# roaster3.net
KiCad netlist of a schematic drawn in EAGLE
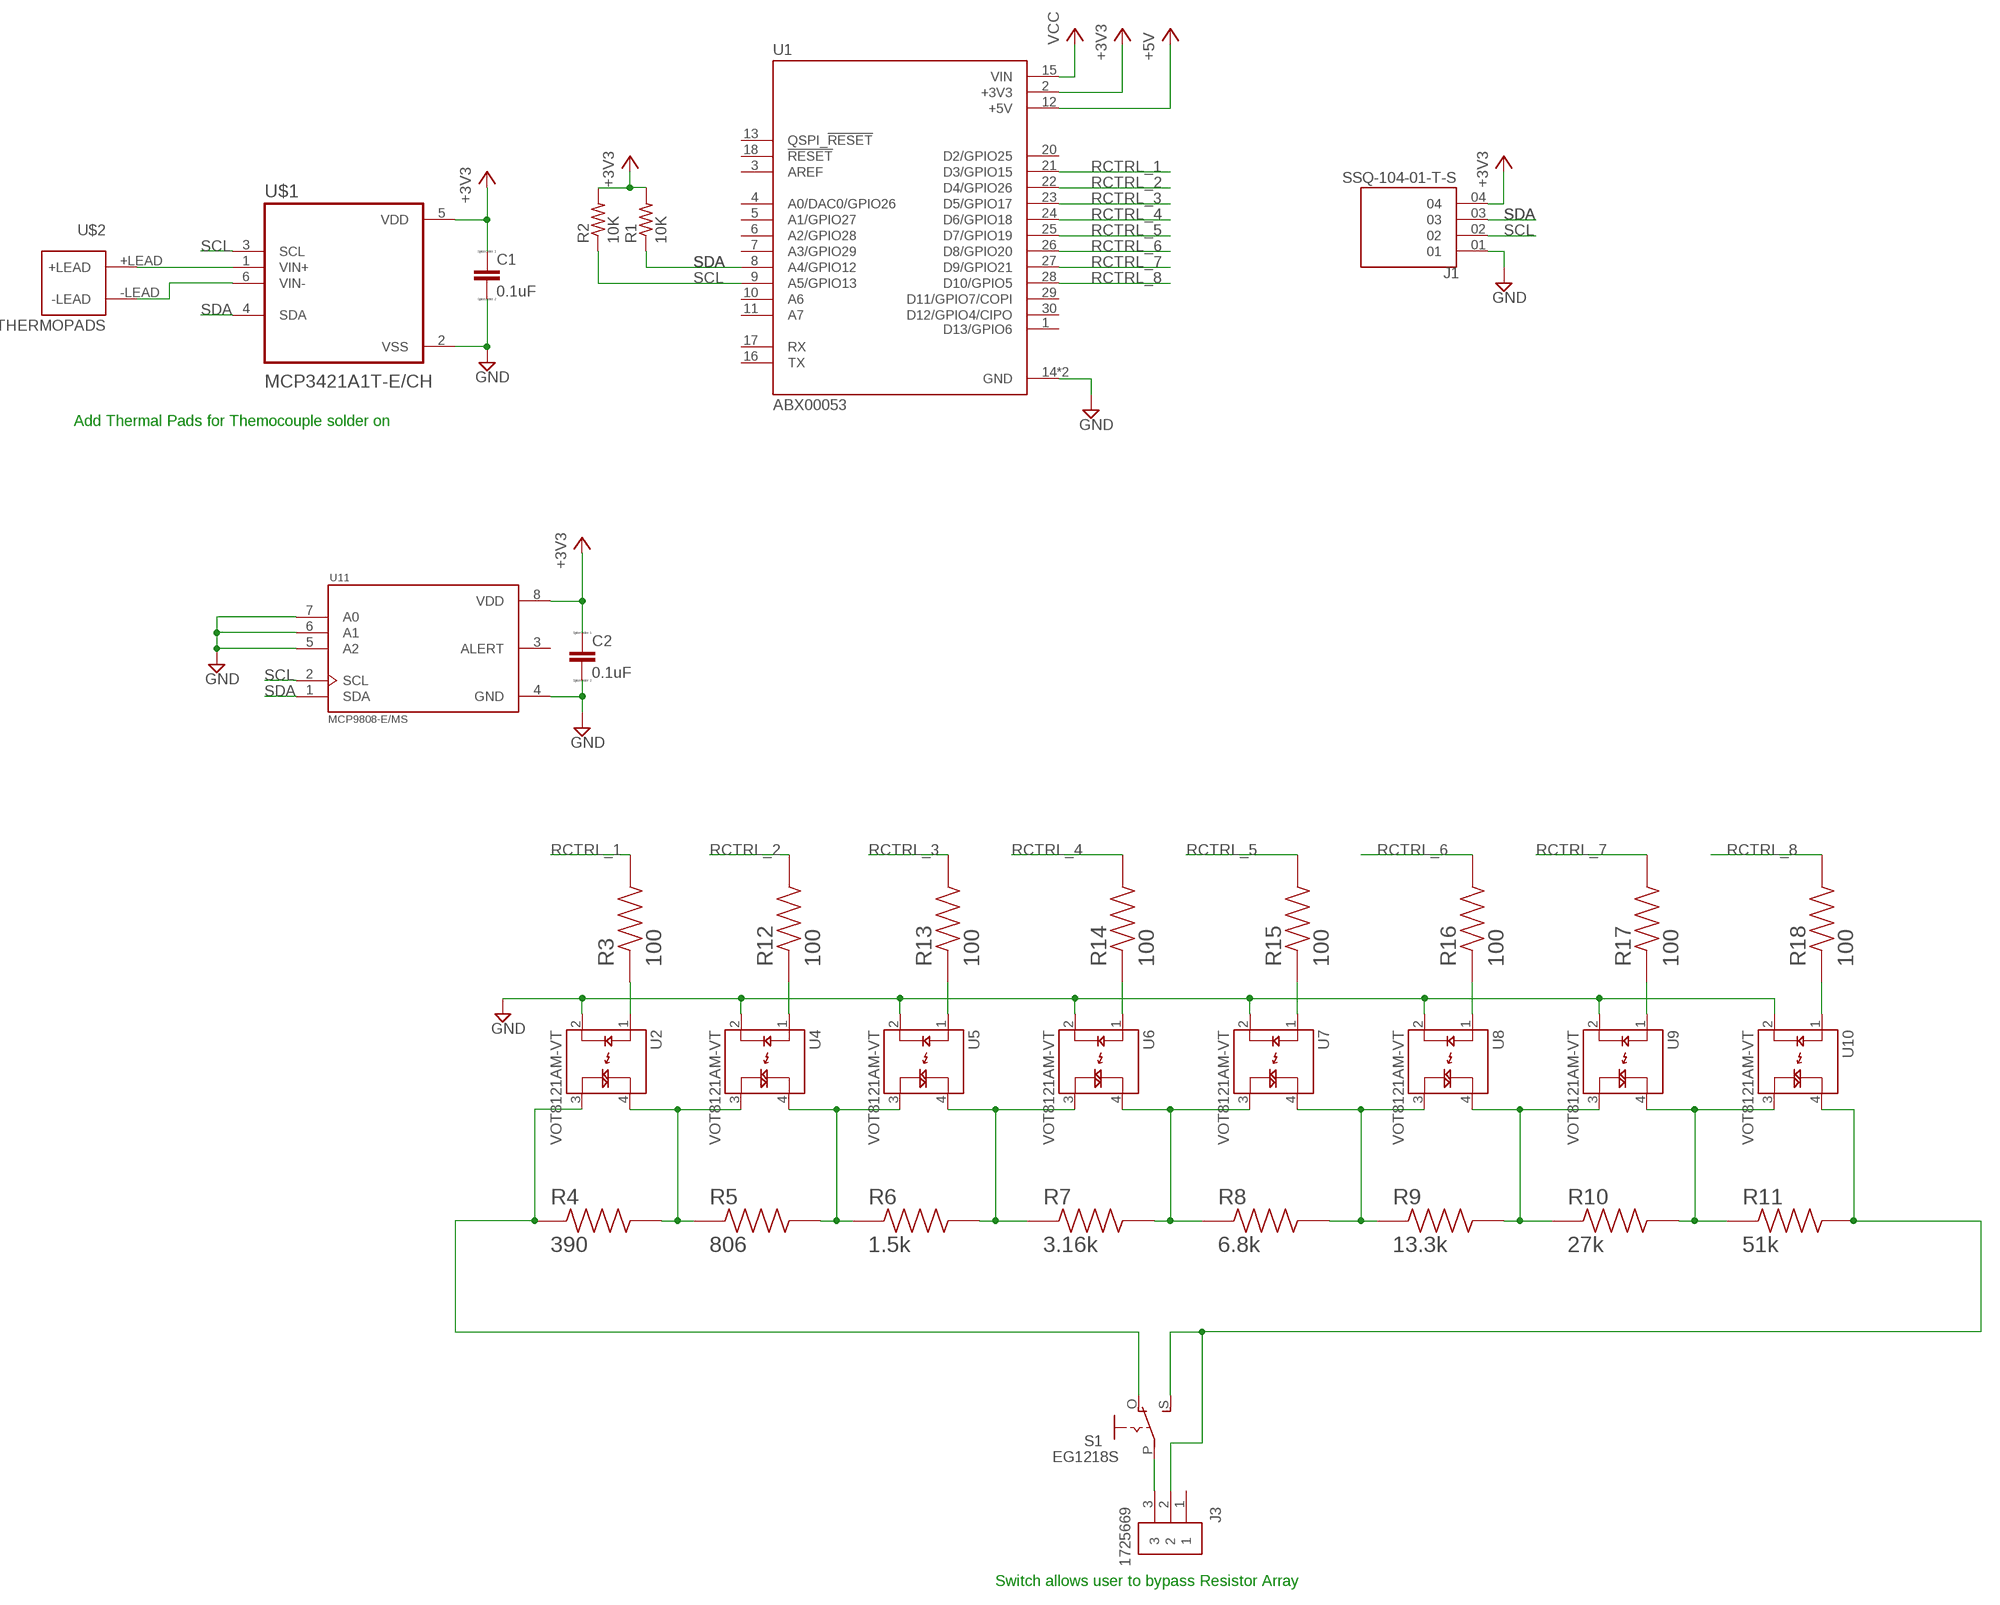
[diagram p0: schematic, sheet 1]

(export (version "E")
  (design (tool "Eeschema 10.0.6"))
  (components
    (comp (ref "C1")
      (value "0.1uF")
      (footprint "eagle-import:RUNJUMP_C0603")
      (fields (field (name "MFR") "Samsung Electro-Mechanics") (field (name "VOLTAGE") "25V"))
      (libsource (lib "eagle-import") (part "RUNJUMP_CAPACITOR-0603-0.1UF-DECOUPLING"))
    )
    (comp (ref "C2")
      (value "0.1uF")
      (footprint "eagle-import:RUNJUMP_C0603")
      (fields (field (name "MFR") "Samsung Electro-Mechanics") (field (name "VOLTAGE") "25V"))
      (libsource (lib "eagle-import") (part "RUNJUMP_CAPACITOR-0603-0.1UF-DECOUPLING"))
    )
    (comp (ref "J1")
      (value "SSQ-104-01-T-S")
      (footprint "eagle-import:SAMTEC_SSQ-104-01-T-S")
      (fields (field (name "MF") "Samtec Inc."))
      (libsource (lib "eagle-import") (part "SSQ-104-01-T-S"))
    )
    (comp (ref "J3")
      (value "1725669")
      (footprint "eagle-import:PHOENIX_1725669")
      (fields (field (name "MF") "Phoenix Contact"))
      (libsource (lib "eagle-import") (part "1725669"))
    )
    (comp (ref "R1")
      (value "10K")
      (footprint "eagle-import:RUNJUMP_R0603")
      (fields (field (name "MFR") "Samsung Electro-Mechanics") (field (name "TOLERANCE") "5%"))
      (libsource (lib "eagle-import") (part "RUNJUMP_RESISTOR-10K"))
    )
    (comp (ref "R2")
      (value "10K")
      (footprint "eagle-import:RUNJUMP_R0603")
      (fields (field (name "MFR") "Samsung Electro-Mechanics") (field (name "TOLERANCE") "5%"))
      (libsource (lib "eagle-import") (part "RUNJUMP_RESISTOR-10K"))
    )
    (comp (ref "R3")
      (value "100")
      (footprint "eagle-import:RESC1608X55N")
      (fields (field (name "MF") "Yageo") (field (name "MP") "AC0603FR-10100RL"))
      (libsource (lib "eagle-import") (part "AC0603FR-10100RL"))
    )
    (comp (ref "R4")
      (value "390")
      (footprint "eagle-import:RESC6332X70N")
      (fields (field (name "MF") "Stackpole Electronics Inc") (field (name "MP") "RMCF2512JT390R"))
      (libsource (lib "eagle-import") (part "RMCF2512JT390R"))
    )
    (comp (ref "R5")
      (value "806")
      (footprint "eagle-import:RESC6332X70N")
      (libsource (lib "eagle-import") (part "RMCF2512FT806R"))
    )
    (comp (ref "R6")
      (value "1.5k")
      (footprint "eagle-import:RESC6332X70N")
      (fields (field (name "MF") "Stackpole Electronics Inc"))
      (libsource (lib "eagle-import") (part "RMCF2512JT1K50"))
    )
    (comp (ref "R7")
      (value "3.16k")
      (footprint "eagle-import:RESC6332X70N")
      (fields (field (name "MF") "Stackpole Electronics Inc"))
      (libsource (lib "eagle-import") (part "RMCF2512FT3K16"))
    )
    (comp (ref "R8")
      (value "6.8k")
      (footprint "eagle-import:RESC6332X70N")
      (fields (field (name "MF") "Stackpole Electronics Inc"))
      (libsource (lib "eagle-import") (part "RMCF2512JT6K80"))
    )
    (comp (ref "R9")
      (value "13.3k")
      (footprint "eagle-import:RESC6332X70N")
      (fields (field (name "MF") "Stackpole Electronics Inc"))
      (libsource (lib "eagle-import") (part "RMCF2512FT13K3"))
    )
    (comp (ref "R10")
      (value "27k")
      (footprint "eagle-import:RESC6332X70N")
      (fields (field (name "MF") "Stackpole Electronics Inc"))
      (libsource (lib "eagle-import") (part "RMCF2512JT27K0"))
    )
    (comp (ref "R11")
      (value "51k")
      (footprint "eagle-import:RESC6332X70N")
      (fields (field (name "MF") "Stackpole Electronics Inc"))
      (libsource (lib "eagle-import") (part "RMCF2512JT51K0"))
    )
    (comp (ref "R12")
      (value "100")
      (footprint "eagle-import:RESC1608X55N")
      (fields (field (name "MF") "Yageo") (field (name "MP") "AC0603FR-10100RL"))
      (libsource (lib "eagle-import") (part "AC0603FR-10100RL"))
    )
    (comp (ref "R13")
      (value "100")
      (footprint "eagle-import:RESC1608X55N")
      (fields (field (name "MF") "Yageo") (field (name "MP") "AC0603FR-10100RL"))
      (libsource (lib "eagle-import") (part "AC0603FR-10100RL"))
    )
    (comp (ref "R14")
      (value "100")
      (footprint "eagle-import:RESC1608X55N")
      (fields (field (name "MF") "Yageo") (field (name "MP") "AC0603FR-10100RL"))
      (libsource (lib "eagle-import") (part "AC0603FR-10100RL"))
    )
    (comp (ref "R15")
      (value "100")
      (footprint "eagle-import:RESC1608X55N")
      (fields (field (name "MF") "Yageo") (field (name "MP") "AC0603FR-10100RL"))
      (libsource (lib "eagle-import") (part "AC0603FR-10100RL"))
    )
    (comp (ref "R16")
      (value "100")
      (footprint "eagle-import:RESC1608X55N")
      (fields (field (name "MF") "Yageo") (field (name "MP") "AC0603FR-10100RL"))
      (libsource (lib "eagle-import") (part "AC0603FR-10100RL"))
    )
    (comp (ref "R17")
      (value "100")
      (footprint "eagle-import:RESC1608X55N")
      (fields (field (name "MF") "Yageo") (field (name "MP") "AC0603FR-10100RL"))
      (libsource (lib "eagle-import") (part "AC0603FR-10100RL"))
    )
    (comp (ref "R18")
      (value "100")
      (footprint "eagle-import:RESC1608X55N")
      (fields (field (name "MF") "Yageo") (field (name "MP") "AC0603FR-10100RL"))
      (libsource (lib "eagle-import") (part "AC0603FR-10100RL"))
    )
    (comp (ref "S1")
      (value "EG1218S")
      (footprint "eagle-import:EG1218")
      (fields (field (name "MF") "E-Switch") (field (name "MP") "EG1218."))
      (libsource (lib "eagle-import") (part "EG1218S"))
    )
    (comp (ref "U$1")
      (value "MCP3421A1T-E/CH")
      (footprint "eagle-import:SOT95P280X145-6N")
      (fields (field (name "MF") "Microchip Technology"))
      (libsource (lib "eagle-import") (part "MCP3421A1T-E/CH"))
    )
    (comp (ref "U$2")
      (value "THERMOPADS")
      (footprint "eagle-import:THERMOPADS")
      (libsource (lib "eagle-import") (part "THERMOPADS"))
    )
    (comp (ref "U1")
      (value "ABX00053")
      (footprint "eagle-import:MODULE_ABX00053")
      (fields (field (name "DIGI-KEY_PART_NUMBER") "1050-ABX00053-ND") (field (name "MF") "Arduino"))
      (libsource (lib "eagle-import") (part "ABX00053"))
    )
    (comp (ref "U2")
      (value "VOT8121AM-VT")
      (footprint "eagle-import:SOIC254P675X240-4N")
      (fields (field (name "MF") "Vishay Semiconductor Opto Division"))
      (libsource (lib "eagle-import") (part "VOT8121AM-VT"))
    )
    (comp (ref "U4")
      (value "VOT8121AM-VT")
      (footprint "eagle-import:SOIC254P675X240-4N")
      (fields (field (name "MF") "Vishay Semiconductor Opto Division"))
      (libsource (lib "eagle-import") (part "VOT8121AM-VT"))
    )
    (comp (ref "U5")
      (value "VOT8121AM-VT")
      (footprint "eagle-import:SOIC254P675X240-4N")
      (fields (field (name "MF") "Vishay Semiconductor Opto Division"))
      (libsource (lib "eagle-import") (part "VOT8121AM-VT"))
    )
    (comp (ref "U6")
      (value "VOT8121AM-VT")
      (footprint "eagle-import:SOIC254P675X240-4N")
      (fields (field (name "MF") "Vishay Semiconductor Opto Division"))
      (libsource (lib "eagle-import") (part "VOT8121AM-VT"))
    )
    (comp (ref "U7")
      (value "VOT8121AM-VT")
      (footprint "eagle-import:SOIC254P675X240-4N")
      (fields (field (name "MF") "Vishay Semiconductor Opto Division"))
      (libsource (lib "eagle-import") (part "VOT8121AM-VT"))
    )
    (comp (ref "U8")
      (value "VOT8121AM-VT")
      (footprint "eagle-import:SOIC254P675X240-4N")
      (fields (field (name "MF") "Vishay Semiconductor Opto Division"))
      (libsource (lib "eagle-import") (part "VOT8121AM-VT"))
    )
    (comp (ref "U9")
      (value "VOT8121AM-VT")
      (footprint "eagle-import:SOIC254P675X240-4N")
      (fields (field (name "MF") "Vishay Semiconductor Opto Division"))
      (libsource (lib "eagle-import") (part "VOT8121AM-VT"))
    )
    (comp (ref "U10")
      (value "VOT8121AM-VT")
      (footprint "eagle-import:SOIC254P675X240-4N")
      (fields (field (name "MF") "Vishay Semiconductor Opto Division"))
      (libsource (lib "eagle-import") (part "VOT8121AM-VT"))
    )
    (comp (ref "U11")
      (value "MCP9808-E/MS")
      (footprint "eagle-import:SOP65P490X110-8N")
      (fields (field (name "MF") "Microchip"))
      (libsource (lib "eagle-import") (part "MCP9808-E/MS"))
    )
  )
  (nets
    (net (code "1") (name "+3V3") (class "Default")
      (node (ref "C1") (pin "1") (pinfunction "1_1") (pintype "passive"))
      (node (ref "C2") (pin "1") (pinfunction "1_1") (pintype "passive"))
      (node (ref "J1") (pin "04") (pinfunction "04_04") (pintype "passive"))
      (node (ref "R1") (pin "2") (pinfunction "2_2") (pintype "passive"))
      (node (ref "R2") (pin "2") (pinfunction "2_2") (pintype "passive"))
      (node (ref "U$1") (pin "5") (pinfunction "VDD_5") (pintype "power_in"))
      (node (ref "U1") (pin "2") (pinfunction "+3V3_2") (pintype "power_in"))
      (node (ref "U11") (pin "8") (pinfunction "VDD_8") (pintype "power_in"))
    )
    (net (code "2") (name "+5V") (class "Default")
      (node (ref "U1") (pin "12") (pinfunction "+5V_12") (pintype "power_in"))
    )
    (net (code "3") (name "/RCTRL_1") (class "Default")
      (node (ref "R3") (pin "2") (pinfunction "2_2") (pintype "passive"))
      (node (ref "U1") (pin "21") (pinfunction "D3/GPIO15_21") (pintype "bidirectional"))
    )
    (net (code "4") (name "/RCTRL_2") (class "Default")
      (node (ref "R12") (pin "2") (pinfunction "2_2") (pintype "passive"))
      (node (ref "U1") (pin "22") (pinfunction "D4/GPIO26_22") (pintype "bidirectional"))
    )
    (net (code "5") (name "/RCTRL_3") (class "Default")
      (node (ref "R13") (pin "2") (pinfunction "2_2") (pintype "passive"))
      (node (ref "U1") (pin "23") (pinfunction "D5/GPIO17_23") (pintype "bidirectional"))
    )
    (net (code "6") (name "/RCTRL_4") (class "Default")
      (node (ref "R14") (pin "2") (pinfunction "2_2") (pintype "passive"))
      (node (ref "U1") (pin "24") (pinfunction "D6/GPIO18_24") (pintype "bidirectional"))
    )
    (net (code "7") (name "/RCTRL_5") (class "Default")
      (node (ref "R15") (pin "2") (pinfunction "2_2") (pintype "passive"))
      (node (ref "U1") (pin "25") (pinfunction "D7/GPIO19_25") (pintype "bidirectional"))
    )
    (net (code "8") (name "/RCTRL_6") (class "Default")
      (node (ref "R16") (pin "2") (pinfunction "2_2") (pintype "passive"))
      (node (ref "U1") (pin "26") (pinfunction "D8/GPIO20_26") (pintype "bidirectional"))
    )
    (net (code "9") (name "/RCTRL_7") (class "Default")
      (node (ref "R17") (pin "2") (pinfunction "2_2") (pintype "passive"))
      (node (ref "U1") (pin "27") (pinfunction "D9/GPIO21_27") (pintype "bidirectional"))
    )
    (net (code "10") (name "/RCTRL_8") (class "Default")
      (node (ref "R18") (pin "2") (pinfunction "2_2") (pintype "passive"))
      (node (ref "U1") (pin "28") (pinfunction "D10/GPIO5_28") (pintype "bidirectional"))
    )
    (net (code "11") (name "/SCL") (class "Default")
      (node (ref "J1") (pin "02") (pinfunction "02_02") (pintype "passive"))
      (node (ref "R2") (pin "1") (pinfunction "1_1") (pintype "passive"))
      (node (ref "U$1") (pin "3") (pinfunction "SCL_3") (pintype "input"))
      (node (ref "U1") (pin "9") (pinfunction "A5/GPIO13_9") (pintype "bidirectional"))
      (node (ref "U11") (pin "2") (pinfunction "SCL_2") (pintype "input"))
    )
    (net (code "12") (name "/SDA") (class "Default")
      (node (ref "J1") (pin "03") (pinfunction "03_03") (pintype "passive"))
      (node (ref "R1") (pin "1") (pinfunction "1_1") (pintype "passive"))
      (node (ref "U$1") (pin "4") (pinfunction "SDA_4") (pintype "bidirectional"))
      (node (ref "U1") (pin "8") (pinfunction "A4/GPIO12_8") (pintype "bidirectional"))
      (node (ref "U11") (pin "1") (pinfunction "SDA_1") (pintype "bidirectional"))
    )
    (net (code "13") (name "GND") (class "Default")
      (node (ref "C1") (pin "2") (pinfunction "2_2") (pintype "passive"))
      (node (ref "C2") (pin "2") (pinfunction "2_2") (pintype "passive"))
      (node (ref "J1") (pin "01") (pinfunction "01_01") (pintype "passive"))
      (node (ref "U$1") (pin "2") (pinfunction "VSS_2") (pintype "power_in"))
      (node (ref "U1") (pin "14") (pinfunction "GND_14") (pintype "power_in"))
      (node (ref "U1") (pin "19") (pinfunction "GND_19") (pintype "power_in"))
      (node (ref "U10") (pin "2") (pinfunction "C_2") (pintype "passive"))
      (node (ref "U11") (pin "4") (pinfunction "GND_4") (pintype "power_in"))
      (node (ref "U11") (pin "5") (pinfunction "A2_5") (pintype "input"))
      (node (ref "U11") (pin "6") (pinfunction "A1_6") (pintype "input"))
      (node (ref "U11") (pin "7") (pinfunction "A0_7") (pintype "input"))
      (node (ref "U2") (pin "2") (pinfunction "C_2") (pintype "passive"))
      (node (ref "U4") (pin "2") (pinfunction "C_2") (pintype "passive"))
      (node (ref "U5") (pin "2") (pinfunction "C_2") (pintype "passive"))
      (node (ref "U6") (pin "2") (pinfunction "C_2") (pintype "passive"))
      (node (ref "U7") (pin "2") (pinfunction "C_2") (pintype "passive"))
      (node (ref "U8") (pin "2") (pinfunction "C_2") (pintype "passive"))
      (node (ref "U9") (pin "2") (pinfunction "C_2") (pintype "passive"))
    )
    (net (code "14") (name "Net-(J3-Pad3)") (class "Default")
      (node (ref "J3") (pin "3") (pinfunction "3_3") (pintype "passive"))
      (node (ref "S1") (pin "P") (pinfunction "P_P") (pintype "passive"))
    )
    (net (code "15") (name "Net-(U$1-VIN+)") (class "Default")
      (node (ref "U$1") (pin "1") (pinfunction "VIN+_1") (pintype "input"))
      (node (ref "U$2") (pin "+LEAD") (pinfunction "+LEAD_+LEAD") (pintype "bidirectional"))
    )
    (net (code "16") (name "Net-(U$1-VIN-)") (class "Default")
      (node (ref "U$1") (pin "6") (pinfunction "VIN-_6") (pintype "input"))
      (node (ref "U$2") (pin "-LEAD") (pinfunction "-LEAD_-LEAD") (pintype "bidirectional"))
    )
    (net (code "17") (name "Net-(U2-A)") (class "Default")
      (node (ref "R3") (pin "1") (pinfunction "1_1") (pintype "passive"))
      (node (ref "U2") (pin "1") (pinfunction "A_1") (pintype "passive"))
    )
    (net (code "18") (name "Net-(U2-MT1)") (class "Default")
      (node (ref "R4") (pin "1") (pinfunction "1_1") (pintype "passive"))
      (node (ref "S1") (pin "O") (pinfunction "O_O") (pintype "passive"))
      (node (ref "U2") (pin "3") (pinfunction "MT1_3") (pintype "passive"))
    )
    (net (code "19") (name "Net-(U2-MT2)") (class "Default")
      (node (ref "R4") (pin "2") (pinfunction "2_2") (pintype "passive"))
      (node (ref "R5") (pin "1") (pinfunction "1_1") (pintype "passive"))
      (node (ref "U2") (pin "4") (pinfunction "MT2_4") (pintype "passive"))
      (node (ref "U4") (pin "3") (pinfunction "MT1_3") (pintype "passive"))
    )
    (net (code "20") (name "Net-(U4-A)") (class "Default")
      (node (ref "R12") (pin "1") (pinfunction "1_1") (pintype "passive"))
      (node (ref "U4") (pin "1") (pinfunction "A_1") (pintype "passive"))
    )
    (net (code "21") (name "Net-(U4-MT2)") (class "Default")
      (node (ref "R5") (pin "2") (pinfunction "2_2") (pintype "passive"))
      (node (ref "R6") (pin "1") (pinfunction "1_1") (pintype "passive"))
      (node (ref "U4") (pin "4") (pinfunction "MT2_4") (pintype "passive"))
      (node (ref "U5") (pin "3") (pinfunction "MT1_3") (pintype "passive"))
    )
    (net (code "22") (name "Net-(U5-A)") (class "Default")
      (node (ref "R13") (pin "1") (pinfunction "1_1") (pintype "passive"))
      (node (ref "U5") (pin "1") (pinfunction "A_1") (pintype "passive"))
    )
    (net (code "23") (name "Net-(U5-MT2)") (class "Default")
      (node (ref "R6") (pin "2") (pinfunction "2_2") (pintype "passive"))
      (node (ref "R7") (pin "1") (pinfunction "1_1") (pintype "passive"))
      (node (ref "U5") (pin "4") (pinfunction "MT2_4") (pintype "passive"))
      (node (ref "U6") (pin "3") (pinfunction "MT1_3") (pintype "passive"))
    )
    (net (code "24") (name "Net-(U6-A)") (class "Default")
      (node (ref "R14") (pin "1") (pinfunction "1_1") (pintype "passive"))
      (node (ref "U6") (pin "1") (pinfunction "A_1") (pintype "passive"))
    )
    (net (code "25") (name "Net-(U6-MT2)") (class "Default")
      (node (ref "R7") (pin "2") (pinfunction "2_2") (pintype "passive"))
      (node (ref "R8") (pin "1") (pinfunction "1_1") (pintype "passive"))
      (node (ref "U6") (pin "4") (pinfunction "MT2_4") (pintype "passive"))
      (node (ref "U7") (pin "3") (pinfunction "MT1_3") (pintype "passive"))
    )
    (net (code "26") (name "Net-(U7-A)") (class "Default")
      (node (ref "R15") (pin "1") (pinfunction "1_1") (pintype "passive"))
      (node (ref "U7") (pin "1") (pinfunction "A_1") (pintype "passive"))
    )
    (net (code "27") (name "Net-(U7-MT2)") (class "Default")
      (node (ref "R8") (pin "2") (pinfunction "2_2") (pintype "passive"))
      (node (ref "R9") (pin "1") (pinfunction "1_1") (pintype "passive"))
      (node (ref "U7") (pin "4") (pinfunction "MT2_4") (pintype "passive"))
      (node (ref "U8") (pin "3") (pinfunction "MT1_3") (pintype "passive"))
    )
    (net (code "28") (name "Net-(U8-A)") (class "Default")
      (node (ref "R16") (pin "1") (pinfunction "1_1") (pintype "passive"))
      (node (ref "U8") (pin "1") (pinfunction "A_1") (pintype "passive"))
    )
    (net (code "29") (name "Net-(U8-MT2)") (class "Default")
      (node (ref "R10") (pin "1") (pinfunction "1_1") (pintype "passive"))
      (node (ref "R9") (pin "2") (pinfunction "2_2") (pintype "passive"))
      (node (ref "U8") (pin "4") (pinfunction "MT2_4") (pintype "passive"))
      (node (ref "U9") (pin "3") (pinfunction "MT1_3") (pintype "passive"))
    )
    (net (code "30") (name "Net-(U9-A)") (class "Default")
      (node (ref "R17") (pin "1") (pinfunction "1_1") (pintype "passive"))
      (node (ref "U9") (pin "1") (pinfunction "A_1") (pintype "passive"))
    )
    (net (code "31") (name "Net-(U10-A)") (class "Default")
      (node (ref "R18") (pin "1") (pinfunction "1_1") (pintype "passive"))
      (node (ref "U10") (pin "1") (pinfunction "A_1") (pintype "passive"))
    )
    (net (code "32") (name "Net-(U10-MT1)") (class "Default")
      (node (ref "R10") (pin "2") (pinfunction "2_2") (pintype "passive"))
      (node (ref "R11") (pin "1") (pinfunction "1_1") (pintype "passive"))
      (node (ref "U10") (pin "3") (pinfunction "MT1_3") (pintype "passive"))
      (node (ref "U9") (pin "4") (pinfunction "MT2_4") (pintype "passive"))
    )
    (net (code "33") (name "Net-(U10-MT2)") (class "Default")
      (node (ref "J3") (pin "2") (pinfunction "2_2") (pintype "passive"))
      (node (ref "R11") (pin "2") (pinfunction "2_2") (pintype "passive"))
      (node (ref "S1") (pin "S") (pinfunction "S_S") (pintype "passive"))
      (node (ref "U10") (pin "4") (pinfunction "MT2_4") (pintype "passive"))
    )
    (net (code "34") (name "VCC") (class "Default")
      (node (ref "U1") (pin "15") (pinfunction "VIN_15") (pintype "power_in"))
    )
    (net (code "35") (name "unconnected-(J3-Pad1)") (class "Default")
      (node (ref "J3") (pin "1") (pinfunction "1_1") (pintype "passive"))
    )
    (net (code "36") (name "unconnected-(U1-A0{slash}DAC0{slash}GPIO26-Pad4)") (class "Default")
      (node (ref "U1") (pin "4") (pinfunction "A0/DAC0/GPIO26_4") (pintype "bidirectional"))
    )
    (net (code "37") (name "unconnected-(U1-A1{slash}GPIO27-Pad5)") (class "Default")
      (node (ref "U1") (pin "5") (pinfunction "A1/GPIO27_5") (pintype "bidirectional"))
    )
    (net (code "38") (name "unconnected-(U1-A2{slash}GPIO28-Pad6)") (class "Default")
      (node (ref "U1") (pin "6") (pinfunction "A2/GPIO28_6") (pintype "bidirectional"))
    )
    (net (code "39") (name "unconnected-(U1-A3{slash}GPIO29-Pad7)") (class "Default")
      (node (ref "U1") (pin "7") (pinfunction "A3/GPIO29_7") (pintype "bidirectional"))
    )
    (net (code "40") (name "unconnected-(U1-A6-Pad10)") (class "Default")
      (node (ref "U1") (pin "10") (pinfunction "A6_10") (pintype "bidirectional"))
    )
    (net (code "41") (name "unconnected-(U1-A7-Pad11)") (class "Default")
      (node (ref "U1") (pin "11") (pinfunction "A7_11") (pintype "bidirectional"))
    )
    (net (code "42") (name "unconnected-(U1-AREF-Pad3)") (class "Default")
      (node (ref "U1") (pin "3") (pinfunction "AREF_3") (pintype "bidirectional"))
    )
    (net (code "43") (name "unconnected-(U1-D2{slash}GPIO25-Pad20)") (class "Default")
      (node (ref "U1") (pin "20") (pinfunction "D2/GPIO25_20") (pintype "bidirectional"))
    )
    (net (code "44") (name "unconnected-(U1-D11{slash}GPIO7{slash}COPI-Pad29)") (class "Default")
      (node (ref "U1") (pin "29") (pinfunction "D11/GPIO7/COPI_29") (pintype "bidirectional"))
    )
    (net (code "45") (name "unconnected-(U1-D12{slash}GPIO4{slash}CIPO-Pad30)") (class "Default")
      (node (ref "U1") (pin "30") (pinfunction "D12/GPIO4/CIPO_30") (pintype "bidirectional"))
    )
    (net (code "46") (name "unconnected-(U1-D13{slash}GPIO6-Pad1)") (class "Default")
      (node (ref "U1") (pin "1") (pinfunction "D13/GPIO6_1") (pintype "bidirectional"))
    )
    (net (code "47") (name "unconnected-(U1-QSPI_~{RESET}-Pad13)") (class "Default")
      (node (ref "U1") (pin "13") (pinfunction "QSPI_~{RESET}_13") (pintype "input"))
    )
    (net (code "48") (name "unconnected-(U1-RX-Pad17)") (class "Default")
      (node (ref "U1") (pin "17") (pinfunction "RX_17") (pintype "bidirectional"))
    )
    (net (code "49") (name "unconnected-(U1-TX-Pad16)") (class "Default")
      (node (ref "U1") (pin "16") (pinfunction "TX_16") (pintype "bidirectional"))
    )
    (net (code "50") (name "unconnected-(U1-~{RESET}-Pad18)") (class "Default")
      (node (ref "U1") (pin "18") (pinfunction "~{RESET}_18") (pintype "input"))
    )
    (net (code "51") (name "unconnected-(U11-ALERT-Pad3)") (class "Default")
      (node (ref "U11") (pin "3") (pinfunction "ALERT_3") (pintype "output"))
    )
  )
)
